# Konnektduino_core_Rev_1_0.net
KiCad netlist of a schematic drawn in EAGLE
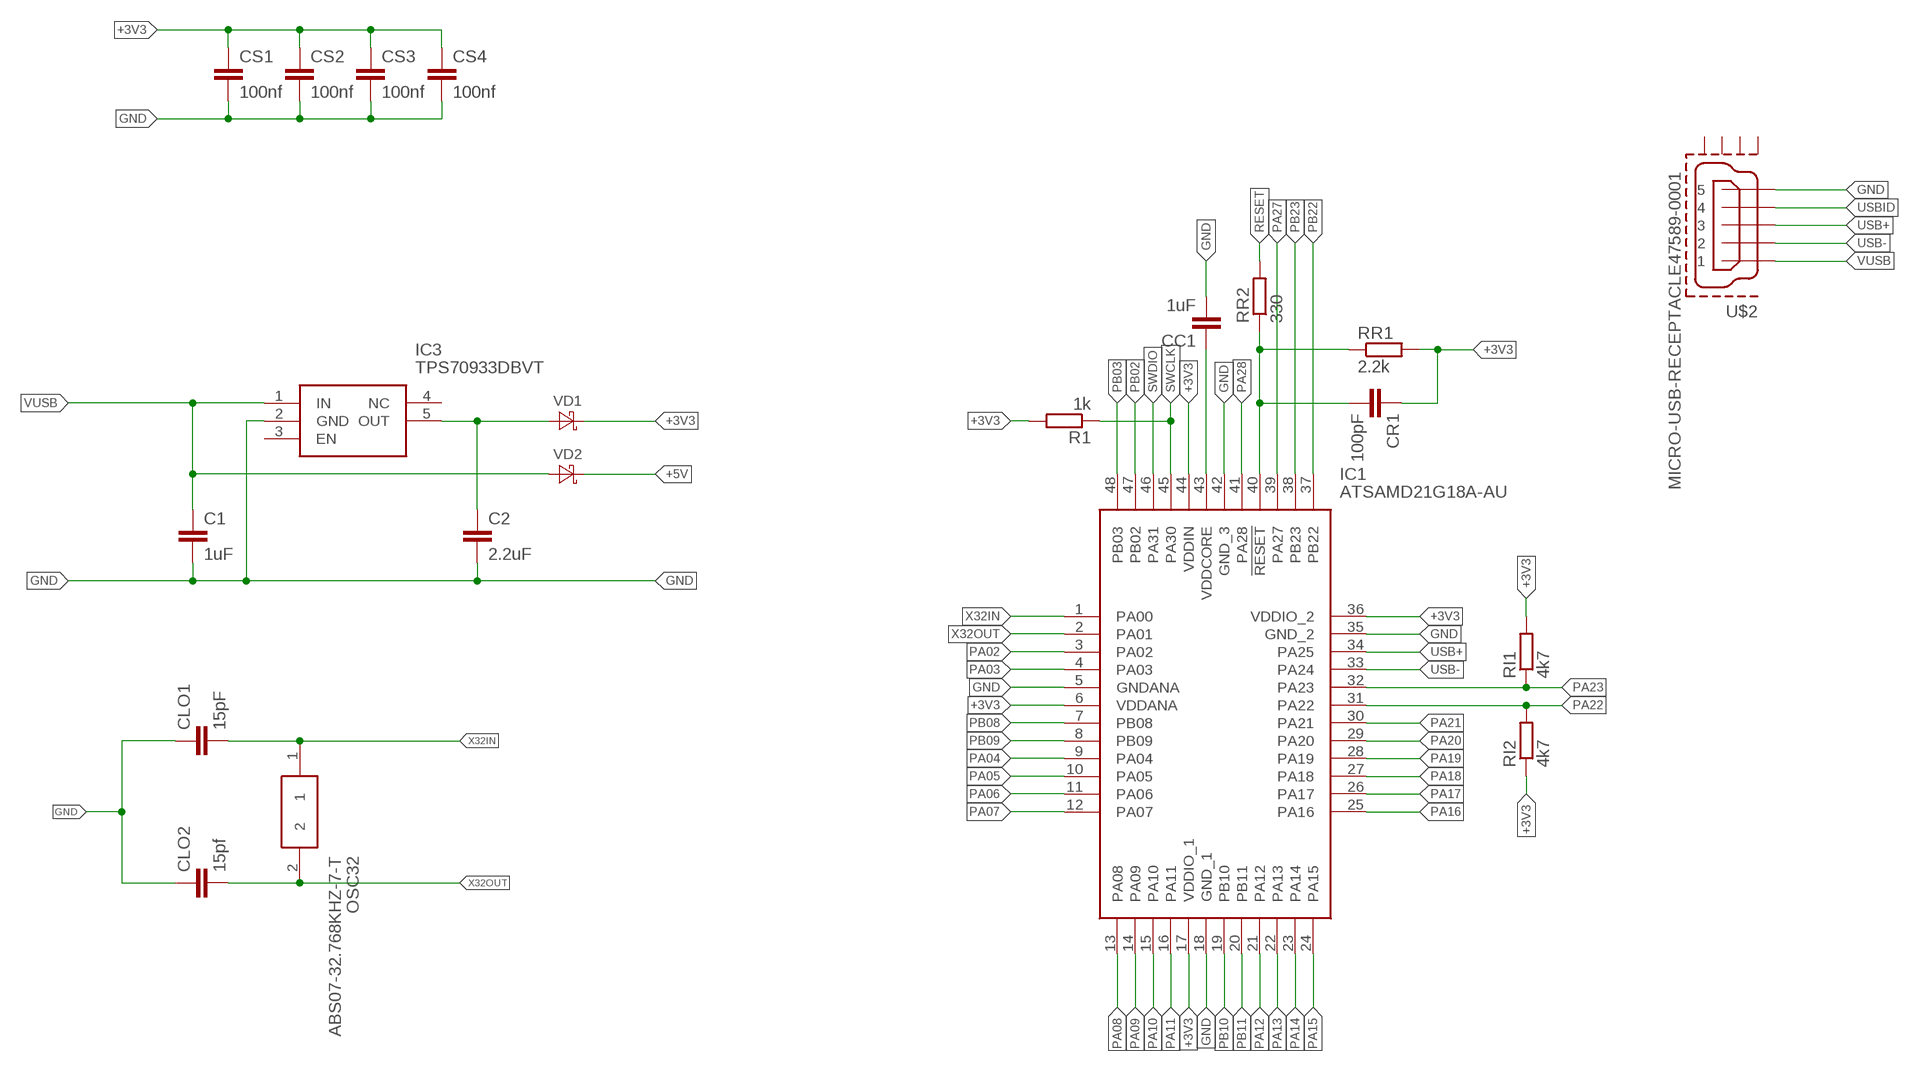
[diagram p0: schematic, sheet 1]

(export (version "E")
  (design (tool "Eeschema 10.0.6"))
  (components
    (comp (ref "C1")
      (value "1uF")
      (footprint "eagle-import:C0603")
      (libsource (lib "eagle-import") (part "C-EUC0603"))
    )
    (comp (ref "C2")
      (value "2.2uF")
      (footprint "eagle-import:C0603")
      (libsource (lib "eagle-import") (part "C-EUC0603"))
    )
    (comp (ref "CC1")
      (value "1uF")
      (footprint "eagle-import:C0603")
      (libsource (lib "eagle-import") (part "C-EUC0603"))
    )
    (comp (ref "CLO1")
      (value "15pF")
      (footprint "eagle-import:C0603")
      (libsource (lib "eagle-import") (part "C-EUC0603"))
    )
    (comp (ref "CLO2")
      (value "15pf")
      (footprint "eagle-import:C0603")
      (libsource (lib "eagle-import") (part "C-EUC0603"))
    )
    (comp (ref "CR1")
      (value "100pF")
      (footprint "eagle-import:C0603")
      (libsource (lib "eagle-import") (part "C-EUC0603"))
    )
    (comp (ref "CS1")
      (value "100nf")
      (footprint "eagle-import:C0603")
      (libsource (lib "eagle-import") (part "C-EUC0603"))
    )
    (comp (ref "CS2")
      (value "100nf")
      (footprint "eagle-import:C0603")
      (libsource (lib "eagle-import") (part "C-EUC0603"))
    )
    (comp (ref "CS3")
      (value "100nf")
      (footprint "eagle-import:C0603")
      (libsource (lib "eagle-import") (part "C-EUC0603"))
    )
    (comp (ref "CS4")
      (value "100nf")
      (footprint "eagle-import:C0603")
      (libsource (lib "eagle-import") (part "C-EUC0603"))
    )
    (comp (ref "IC1")
      (value "ATSAMD21G18A-AU")
      (footprint "eagle-import:QFP50P900X900X120-48N")
      (fields (field (name "RS_PART_NUMBER") "1773799P"))
      (libsource (lib "eagle-import") (part "ATSAMD21G18A-AU"))
    )
    (comp (ref "IC3")
      (value "TPS70933DBVT")
      (footprint "eagle-import:SOT95P280X145-5N")
      (fields (field (name "RS_PART_NUMBER") "8257033P"))
      (libsource (lib "eagle-import") (part "TPS70933DBVT"))
    )
    (comp (ref "OSC32")
      (value "ABS07-32.768KHZ-7-T")
      (footprint "eagle-import:ABS-07")
      (fields (field (name "RS_PART_NUMBER") "1712773P"))
      (libsource (lib "eagle-import") (part "ABS07-32.768KHZ-7-T"))
    )
    (comp (ref "R1")
      (value "1k")
      (footprint "eagle-import:R0603")
      (libsource (lib "eagle-import") (part "R-EU_R0603"))
    )
    (comp (ref "RI1")
      (value "4k7")
      (footprint "eagle-import:R0603")
      (libsource (lib "eagle-import") (part "R-EU_R0603"))
    )
    (comp (ref "RI2")
      (value "4k7")
      (footprint "eagle-import:R0603")
      (libsource (lib "eagle-import") (part "R-EU_R0603"))
    )
    (comp (ref "RR1")
      (value "2.2k")
      (footprint "eagle-import:R0603")
      (libsource (lib "eagle-import") (part "R-EU_R0603"))
    )
    (comp (ref "RR2")
      (value "330")
      (footprint "eagle-import:R0603")
      (libsource (lib "eagle-import") (part "R-EU_R0603"))
    )
    (comp (ref "U$2")
      (value "MICRO-USB-RECEPTACLE47589-0001")
      (footprint "eagle-import:47589-0001")
      (libsource (lib "eagle-import") (part "MICRO-USB-RECEPTACLE47589-0001"))
    )
    (comp (ref "VD1")
      (value "DIODE-SCHOTTKY-0603")
      (footprint "eagle-import:D0603")
      (libsource (lib "eagle-import") (part "DIODE-SCHOTTKY-0603"))
    )
    (comp (ref "VD2")
      (value "DIODE-SCHOTTKY-0603")
      (footprint "eagle-import:D0603")
      (libsource (lib "eagle-import") (part "DIODE-SCHOTTKY-0603"))
    )
  )
  (nets
    (net (code "1") (name "+3V3") (class "Default")
      (node (ref "CR1") (pin "1") (pinfunction "1_1") (pintype "passive"))
      (node (ref "CS1") (pin "1") (pinfunction "1_1") (pintype "passive"))
      (node (ref "CS2") (pin "1") (pinfunction "1_1") (pintype "passive"))
      (node (ref "CS3") (pin "1") (pinfunction "1_1") (pintype "passive"))
      (node (ref "CS4") (pin "1") (pinfunction "1_1") (pintype "passive"))
      (node (ref "IC1") (pin "17") (pinfunction "VDDIO_1_17") (pintype "bidirectional"))
      (node (ref "IC1") (pin "36") (pinfunction "VDDIO_2_36") (pintype "bidirectional"))
      (node (ref "IC1") (pin "44") (pinfunction "VDDIN_44") (pintype "bidirectional"))
      (node (ref "IC1") (pin "6") (pinfunction "VDDANA_6") (pintype "bidirectional"))
      (node (ref "R1") (pin "2") (pinfunction "2_2") (pintype "passive"))
      (node (ref "RI1") (pin "2") (pinfunction "2_2") (pintype "passive"))
      (node (ref "RI2") (pin "1") (pinfunction "1_1") (pintype "passive"))
      (node (ref "RR1") (pin "2") (pinfunction "2_2") (pintype "passive"))
      (node (ref "VD1") (pin "C") (pinfunction "C_C") (pintype "passive"))
    )
    (net (code "2") (name "+5V") (class "Default")
      (node (ref "VD2") (pin "C") (pinfunction "C_C") (pintype "passive"))
    )
    (net (code "3") (name "GND") (class "Default")
      (node (ref "C1") (pin "2") (pinfunction "2_2") (pintype "passive"))
      (node (ref "C2") (pin "2") (pinfunction "2_2") (pintype "passive"))
      (node (ref "CC1") (pin "2") (pinfunction "2_2") (pintype "passive"))
      (node (ref "CLO1") (pin "1") (pinfunction "1_1") (pintype "passive"))
      (node (ref "CLO2") (pin "1") (pinfunction "1_1") (pintype "passive"))
      (node (ref "CS1") (pin "2") (pinfunction "2_2") (pintype "passive"))
      (node (ref "CS2") (pin "2") (pinfunction "2_2") (pintype "passive"))
      (node (ref "CS3") (pin "2") (pinfunction "2_2") (pintype "passive"))
      (node (ref "CS4") (pin "2") (pinfunction "2_2") (pintype "passive"))
      (node (ref "IC1") (pin "18") (pinfunction "GND_1_18") (pintype "bidirectional"))
      (node (ref "IC1") (pin "35") (pinfunction "GND_2_35") (pintype "bidirectional"))
      (node (ref "IC1") (pin "42") (pinfunction "GND_3_42") (pintype "bidirectional"))
      (node (ref "IC1") (pin "5") (pinfunction "GNDANA_5") (pintype "bidirectional"))
      (node (ref "IC3") (pin "2") (pinfunction "GND_2") (pintype "bidirectional"))
      (node (ref "U$2") (pin "5") (pinfunction "5_5") (pintype "input"))
    )
    (net (code "4") (name "Net-(IC1-VDDCORE)") (class "Default")
      (node (ref "CC1") (pin "1") (pinfunction "1_1") (pintype "passive"))
      (node (ref "IC1") (pin "43") (pinfunction "VDDCORE_43") (pintype "bidirectional"))
    )
    (net (code "5") (name "Net-(IC1-~{RESET})") (class "Default")
      (node (ref "CR1") (pin "2") (pinfunction "2_2") (pintype "passive"))
      (node (ref "IC1") (pin "40") (pinfunction "~{RESET}_40") (pintype "bidirectional"))
      (node (ref "RR1") (pin "1") (pinfunction "1_1") (pintype "passive"))
      (node (ref "RR2") (pin "1") (pinfunction "1_1") (pintype "passive"))
    )
    (net (code "6") (name "Net-(IC3-OUT)") (class "Default")
      (node (ref "C2") (pin "1") (pinfunction "1_1") (pintype "passive"))
      (node (ref "IC3") (pin "5") (pinfunction "OUT_5") (pintype "bidirectional"))
      (node (ref "VD1") (pin "A") (pinfunction "A_A") (pintype "passive"))
    )
    (net (code "7") (name "PA02") (class "Default")
      (node (ref "IC1") (pin "3") (pinfunction "PA02_3") (pintype "bidirectional"))
    )
    (net (code "8") (name "PA03") (class "Default")
      (node (ref "IC1") (pin "4") (pinfunction "PA03_4") (pintype "bidirectional"))
    )
    (net (code "9") (name "PA04") (class "Default")
      (node (ref "IC1") (pin "9") (pinfunction "PA04_9") (pintype "bidirectional"))
    )
    (net (code "10") (name "PA05") (class "Default")
      (node (ref "IC1") (pin "10") (pinfunction "PA05_10") (pintype "bidirectional"))
    )
    (net (code "11") (name "PA06") (class "Default")
      (node (ref "IC1") (pin "11") (pinfunction "PA06_11") (pintype "bidirectional"))
    )
    (net (code "12") (name "PA07") (class "Default")
      (node (ref "IC1") (pin "12") (pinfunction "PA07_12") (pintype "bidirectional"))
    )
    (net (code "13") (name "PA08") (class "Default")
      (node (ref "IC1") (pin "13") (pinfunction "PA08_13") (pintype "bidirectional"))
    )
    (net (code "14") (name "PA09") (class "Default")
      (node (ref "IC1") (pin "14") (pinfunction "PA09_14") (pintype "bidirectional"))
    )
    (net (code "15") (name "PA10") (class "Default")
      (node (ref "IC1") (pin "15") (pinfunction "PA10_15") (pintype "bidirectional"))
    )
    (net (code "16") (name "PA11") (class "Default")
      (node (ref "IC1") (pin "16") (pinfunction "PA11_16") (pintype "bidirectional"))
    )
    (net (code "17") (name "PA12") (class "Default")
      (node (ref "IC1") (pin "21") (pinfunction "PA12_21") (pintype "bidirectional"))
    )
    (net (code "18") (name "PA13") (class "Default")
      (node (ref "IC1") (pin "22") (pinfunction "PA13_22") (pintype "bidirectional"))
    )
    (net (code "19") (name "PA14") (class "Default")
      (node (ref "IC1") (pin "23") (pinfunction "PA14_23") (pintype "bidirectional"))
    )
    (net (code "20") (name "PA15") (class "Default")
      (node (ref "IC1") (pin "24") (pinfunction "PA15_24") (pintype "bidirectional"))
    )
    (net (code "21") (name "PA16") (class "Default")
      (node (ref "IC1") (pin "25") (pinfunction "PA16_25") (pintype "bidirectional"))
    )
    (net (code "22") (name "PA17") (class "Default")
      (node (ref "IC1") (pin "26") (pinfunction "PA17_26") (pintype "bidirectional"))
    )
    (net (code "23") (name "PA18") (class "Default")
      (node (ref "IC1") (pin "27") (pinfunction "PA18_27") (pintype "bidirectional"))
    )
    (net (code "24") (name "PA19") (class "Default")
      (node (ref "IC1") (pin "28") (pinfunction "PA19_28") (pintype "bidirectional"))
    )
    (net (code "25") (name "PA20") (class "Default")
      (node (ref "IC1") (pin "29") (pinfunction "PA20_29") (pintype "bidirectional"))
    )
    (net (code "26") (name "PA21") (class "Default")
      (node (ref "IC1") (pin "30") (pinfunction "PA21_30") (pintype "bidirectional"))
    )
    (net (code "27") (name "PA22") (class "Default")
      (node (ref "IC1") (pin "31") (pinfunction "PA22_31") (pintype "bidirectional"))
      (node (ref "RI2") (pin "2") (pinfunction "2_2") (pintype "passive"))
    )
    (net (code "28") (name "PA23") (class "Default")
      (node (ref "IC1") (pin "32") (pinfunction "PA23_32") (pintype "bidirectional"))
      (node (ref "RI1") (pin "1") (pinfunction "1_1") (pintype "passive"))
    )
    (net (code "29") (name "PA27") (class "Default")
      (node (ref "IC1") (pin "39") (pinfunction "PA27_39") (pintype "bidirectional"))
    )
    (net (code "30") (name "PA28") (class "Default")
      (node (ref "IC1") (pin "41") (pinfunction "PA28_41") (pintype "bidirectional"))
    )
    (net (code "31") (name "PB02") (class "Default")
      (node (ref "IC1") (pin "47") (pinfunction "PB02_47") (pintype "bidirectional"))
    )
    (net (code "32") (name "PB03") (class "Default")
      (node (ref "IC1") (pin "48") (pinfunction "PB03_48") (pintype "bidirectional"))
    )
    (net (code "33") (name "PB08") (class "Default")
      (node (ref "IC1") (pin "7") (pinfunction "PB08_7") (pintype "bidirectional"))
    )
    (net (code "34") (name "PB09") (class "Default")
      (node (ref "IC1") (pin "8") (pinfunction "PB09_8") (pintype "bidirectional"))
    )
    (net (code "35") (name "PB10") (class "Default")
      (node (ref "IC1") (pin "19") (pinfunction "PB10_19") (pintype "bidirectional"))
    )
    (net (code "36") (name "PB11") (class "Default")
      (node (ref "IC1") (pin "20") (pinfunction "PB11_20") (pintype "bidirectional"))
    )
    (net (code "37") (name "PB22") (class "Default")
      (node (ref "IC1") (pin "37") (pinfunction "PB22_37") (pintype "bidirectional"))
    )
    (net (code "38") (name "PB23") (class "Default")
      (node (ref "IC1") (pin "38") (pinfunction "PB23_38") (pintype "bidirectional"))
    )
    (net (code "39") (name "RESET") (class "Default")
      (node (ref "RR2") (pin "2") (pinfunction "2_2") (pintype "passive"))
    )
    (net (code "40") (name "SWCLK") (class "Default")
      (node (ref "IC1") (pin "45") (pinfunction "PA30_45") (pintype "bidirectional"))
      (node (ref "R1") (pin "1") (pinfunction "1_1") (pintype "passive"))
    )
    (net (code "41") (name "SWDIO") (class "Default")
      (node (ref "IC1") (pin "46") (pinfunction "PA31_46") (pintype "bidirectional"))
    )
    (net (code "42") (name "USB+") (class "Default")
      (node (ref "IC1") (pin "34") (pinfunction "PA25_34") (pintype "bidirectional"))
      (node (ref "U$2") (pin "3") (pinfunction "3_3") (pintype "input"))
    )
    (net (code "43") (name "USB-") (class "Default")
      (node (ref "IC1") (pin "33") (pinfunction "PA24_33") (pintype "bidirectional"))
      (node (ref "U$2") (pin "2") (pinfunction "2_2") (pintype "input"))
    )
    (net (code "44") (name "USBID") (class "Default")
      (node (ref "U$2") (pin "4") (pinfunction "4_4") (pintype "input"))
    )
    (net (code "45") (name "VUSB") (class "Default")
      (node (ref "C1") (pin "1") (pinfunction "1_1") (pintype "passive"))
      (node (ref "IC3") (pin "1") (pinfunction "IN_1") (pintype "bidirectional"))
      (node (ref "U$2") (pin "1") (pinfunction "1_1") (pintype "input"))
      (node (ref "VD2") (pin "A") (pinfunction "A_A") (pintype "passive"))
    )
    (net (code "46") (name "X32IN") (class "Default")
      (node (ref "CLO1") (pin "2") (pinfunction "2_2") (pintype "passive"))
      (node (ref "IC1") (pin "1") (pinfunction "PA00_1") (pintype "bidirectional"))
      (node (ref "OSC32") (pin "1") (pinfunction "1_1") (pintype "bidirectional"))
    )
    (net (code "47") (name "X32OUT") (class "Default")
      (node (ref "CLO2") (pin "2") (pinfunction "2_2") (pintype "passive"))
      (node (ref "IC1") (pin "2") (pinfunction "PA01_2") (pintype "bidirectional"))
      (node (ref "OSC32") (pin "2") (pinfunction "2_2") (pintype "bidirectional"))
    )
    (net (code "48") (name "unconnected-(IC3-EN-Pad3)") (class "Default")
      (node (ref "IC3") (pin "3") (pinfunction "EN_3") (pintype "bidirectional"))
    )
    (net (code "49") (name "unconnected-(IC3-NC-Pad4)") (class "Default")
      (node (ref "IC3") (pin "4") (pinfunction "NC_4") (pintype "no_connect"))
    )
    (net (code "50") (name "unconnected-(U$2-GND1-PadCASING1)") (class "Default")
      (node (ref "U$2") (pin "CASING1") (pinfunction "GND1_CASING1") (pintype "bidirectional"))
    )
    (net (code "51") (name "unconnected-(U$2-GND2-PadCASING2)") (class "Default")
      (node (ref "U$2") (pin "CASING2") (pinfunction "GND2_CASING2") (pintype "bidirectional"))
    )
    (net (code "52") (name "unconnected-(U$2-GND3-PadCASING3)") (class "Default")
      (node (ref "U$2") (pin "CASING3") (pinfunction "GND3_CASING3") (pintype "bidirectional"))
    )
    (net (code "53") (name "unconnected-(U$2-GND4-PadCASING4)") (class "Default")
      (node (ref "U$2") (pin "CASING4") (pinfunction "GND4_CASING4") (pintype "bidirectional"))
    )
  )
)
